# Sheet1.net
KiCad netlist of a schematic drawn in Altium Designer
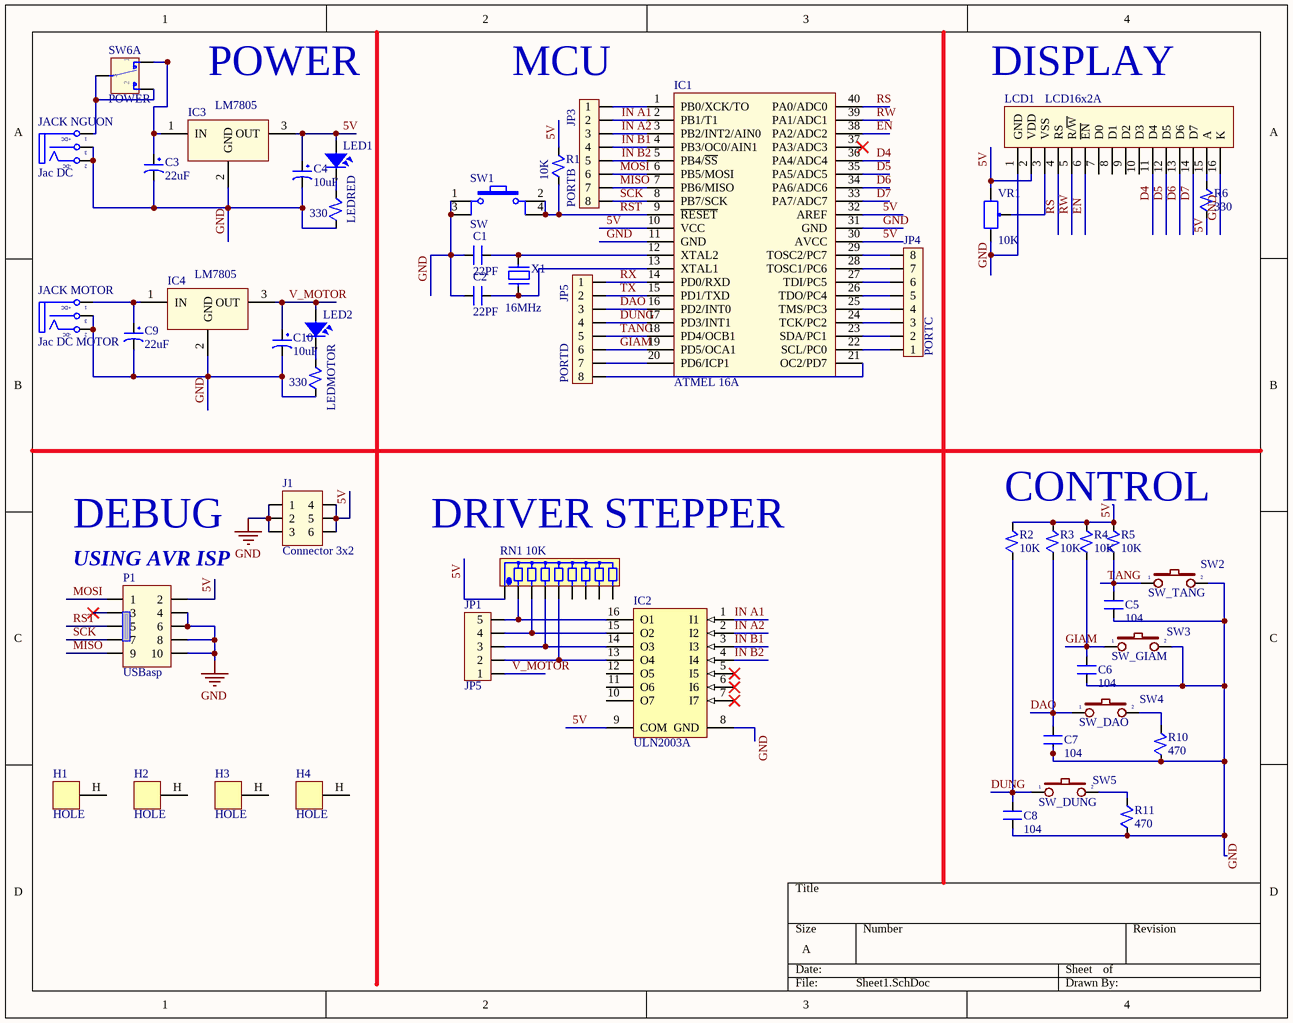
[diagram p0: Sheet1.SchDoc]

(export (version "E")
  (design (tool "Eeschema 10.0.6"))
  (components
    (comp (ref "C1")
      (value "22PF")
      (footprint "SM-0805")
      (description "Cap SMD")
      (libsource (lib "Linhkien69") (part "CM"))
    )
    (comp (ref "C2")
      (value "22PF")
      (footprint "SM-0805")
      (description "Cap SMD")
      (libsource (lib "Linhkien69") (part "CM"))
    )
    (comp (ref "C3")
      (value "22uF")
      (footprint "CP1/2")
      (description "Cap P  0,1uF < 22uF , 16 - 50V")
      (libsource (lib "Linhkien69") (part "CP1"))
    )
    (comp (ref "C4")
      (value "10uF")
      (footprint "CP1/2")
      (description "Cap P  0,1uF < 22uF , 16 - 50V")
      (libsource (lib "Linhkien69") (part "CP1"))
    )
    (comp (ref "C5")
      (value "104")
      (footprint "SM-0805")
      (description "Cap SMD")
      (libsource (lib "Linhkien69") (part "CM"))
    )
    (comp (ref "C6")
      (value "104")
      (footprint "SM-0805")
      (description "Cap SMD")
      (libsource (lib "Linhkien69") (part "CM"))
    )
    (comp (ref "C7")
      (value "104")
      (footprint "SM-0805")
      (description "Cap SMD")
      (libsource (lib "Linhkien69") (part "CM"))
    )
    (comp (ref "C8")
      (value "104")
      (footprint "SM-0805")
      (description "Cap SMD")
      (libsource (lib "Linhkien69") (part "CM"))
    )
    (comp (ref "C9")
      (value "22uF")
      (footprint "CP1/2")
      (description "Cap P  0,1uF < 22uF , 16 - 50V")
      (libsource (lib "Linhkien69") (part "CP1"))
    )
    (comp (ref "C10")
      (value "10uF")
      (footprint "CP1/2")
      (description "Cap P  0,1uF < 22uF , 16 - 50V")
      (libsource (lib "Linhkien69") (part "CP1"))
    )
    (comp (ref "H1") (value "HOLE") (footprint "HOLE") (libsource (lib "ThinhNguyenLib") (part "HOLE")))
    (comp (ref "H2") (value "HOLE") (footprint "HOLE") (libsource (lib "ThinhNguyenLib") (part "HOLE")))
    (comp (ref "H3") (value "HOLE") (footprint "HOLE") (libsource (lib "ThinhNguyenLib") (part "HOLE")))
    (comp (ref "H4") (value "HOLE") (footprint "HOLE") (libsource (lib "ThinhNguyenLib") (part "HOLE")))
    (comp (ref "IC1")
      (value "ATMEL 16A")
      (footprint "DIP40/W0.6")
      (description "8-Bit AVR Microcontroller with 16K Bytes of In-System Programmable Flash Memory")
      (libsource (lib "Linhkien69") (part "Atmega16L"))
    )
    (comp (ref "IC2")
      (value "ULN2003A")
      (footprint "DIP16/W0.3")
      (description "High-Voltage, High-Current Darlington Array")
      (fields (field (name "PUBLISHER") "Altium Limited"))
      (libsource (lib "Linhkien69") (part "ULN2003A"))
    )
    (comp (ref "IC3")
      (value "LM7805")
      (footprint "QTO-220")
      (description "On ap +, from + 5 to + 24VDC")
      (libsource (lib "Linhkien69") (part "LM78xx"))
    )
    (comp (ref "IC4")
      (value "LM7805")
      (footprint "QTO-220")
      (description "On ap +, from + 5 to + 24VDC")
      (libsource (lib "Linhkien69") (part "LM78xx"))
    )
    (comp (ref "J1")
      (value "Connector 3x2")
      (footprint "JP3x2")
      (libsource (lib "Linhkien69") (part "JP3x2"))
    )
    (comp (ref "JACK MOTOR")
      (value "Jac DC MOTOR")
      (footprint "DC-IN")
      (description "Jac DC input")
      (libsource (lib "Linhkien69") (part "DCIN"))
    )
    (comp (ref "JACK NGUON")
      (value "Jac DC")
      (footprint "DC-IN")
      (description "Jac DC input")
      (libsource (lib "Linhkien69") (part "DCIN"))
    )
    (comp (ref "JP1")
      (value "JP5")
      (footprint "CON5")
      (description "Connector 5")
      (libsource (lib "Linhkien69") (part "Con5"))
    )
    (comp (ref "JP3")
      (value "PORTB")
      (footprint "JP_CAI_8")
      (description "JP8 PIN")
      (libsource (lib "") (part "JP8_1"))
    )
    (comp (ref "JP4")
      (value "PORTC")
      (footprint "JP_CAI_8")
      (description "JP8 PIN")
      (libsource (lib "Linhkien69") (part "JP8"))
    )
    (comp (ref "JP5")
      (value "PORTD")
      (footprint "JP_CAI_8")
      (description "JP8 PIN")
      (libsource (lib "") (part "JP8_1"))
    )
    (comp (ref "LCD1")
      (value "LCD16x2A")
      (footprint "LCD16X2N")
      (description "LCD dipslay 16 char, 2 line")
      (libsource (lib "Linhkien69") (part "LCD16x2"))
    )
    (comp (ref "LED1")
      (value "LEDRED")
      (footprint "led5mm_yellow")
      (description "LED Single colour Green and Red")
      (libsource (lib "Linhkien69") (part "LED"))
    )
    (comp (ref "LED2")
      (value "LEDMOTOR")
      (footprint "led5mm_yellow")
      (description "LED Single colour Green and Red")
      (libsource (lib "Linhkien69") (part "LED"))
    )
    (comp (ref "P1")
      (value "USBasp")
      (footprint "IDE_2X5")
      (description "Header 5x2")
      (libsource (lib "Linhkien69") (part "IDE 5x2"))
    )
    (comp (ref "R1")
      (value "10K")
      (footprint "RES_0805")
      (description "res_dan")
      (libsource (lib "Linhkien69") (part "RES_0805"))
    )
    (comp (ref "R2")
      (value "10K")
      (footprint "RES_0805")
      (description "res_dan")
      (libsource (lib "Linhkien69") (part "RES_0805"))
    )
    (comp (ref "R3")
      (value "10K")
      (footprint "RES_0805")
      (description "res_dan")
      (libsource (lib "Linhkien69") (part "RES_0805"))
    )
    (comp (ref "R4")
      (value "10K")
      (footprint "RES_0805")
      (description "res_dan")
      (libsource (lib "Linhkien69") (part "RES_0805"))
    )
    (comp (ref "R5")
      (value "10K")
      (footprint "RES_0805")
      (description "res_dan")
      (libsource (lib "Linhkien69") (part "RES_0805"))
    )
    (comp (ref "R6")
      (value "330")
      (footprint "RES_0805")
      (description "res_dan")
      (libsource (lib "Linhkien69") (part "RES_0805"))
    )
    (comp (ref "R7")
      (value "330")
      (footprint "RES_0805")
      (description "res_dan")
      (libsource (lib "Linhkien69") (part "RES_0805"))
    )
    (comp (ref "R10")
      (value "470")
      (footprint "RES_0805")
      (description "res_dan")
      (libsource (lib "Linhkien69") (part "RES_0805"))
    )
    (comp (ref "R11")
      (value "470")
      (footprint "RES_0805")
      (description "res_dan")
      (libsource (lib "Linhkien69") (part "RES_0805"))
    )
    (comp (ref "R12")
      (value "330")
      (footprint "RES_0805")
      (description "res_dan")
      (libsource (lib "Linhkien69") (part "RES_0805"))
    )
    (comp (ref "RN1")
      (value "10K")
      (footprint "RN8")
      (description "Resistor 8 (Thanh)")
      (libsource (lib "Linhkien69") (part "RN8"))
    )
    (comp (ref "SW1")
      (value "SW")
      (footprint "SW4")
      (description "Switch button 4 pin")
      (libsource (lib "Linhkien69") (part "SW4"))
    )
    (comp (ref "SW2")
      (value "SW_TANG")
      (footprint "SW2")
      (description "Switch button 2 pin")
      (libsource (lib "Linhkien69") (part "SW2"))
    )
    (comp (ref "SW3")
      (value "SW_GIAM")
      (footprint "SW2")
      (description "Switch button 2 pin")
      (libsource (lib "Linhkien69") (part "SW2"))
    )
    (comp (ref "SW4")
      (value "SW_DAO")
      (footprint "SW2")
      (description "Switch button 2 pin")
      (libsource (lib "Linhkien69") (part "SW2"))
    )
    (comp (ref "SW5")
      (value "SW_DUNG")
      (footprint "SW2")
      (description "Switch button 2 pin")
      (libsource (lib "Linhkien69") (part "SW2"))
    )
    (comp (ref "SW6")
      (value "POWER")
      (footprint "SW6")
      (description "SW-DTDP - 6 Pin")
      (libsource (lib "Linhkien69") (part "SW6A"))
    )
    (comp (ref "VR1")
      (value "10K")
      (footprint "VR")
      (description "Var Resistor")
      (libsource (lib "Linhkien69") (part "VR"))
    )
    (comp (ref "X1")
      (value "16MHz")
      (footprint "XT2")
      (description "Crystal For all Crystal 2pin.")
      (libsource (lib "Linhkien69") (part "XT2"))
    )
  )
  (nets
    (net (code "1") (name "/5V") (class "Default")
      (node (ref "C4") (pin "1") (pinfunction "1_1") (pintype "passive"))
      (node (ref "IC1") (pin "10") (pinfunction "VCC_10") (pintype "passive"))
      (node (ref "IC1") (pin "30") (pinfunction "AVCC_30") (pintype "passive"))
      (node (ref "IC1") (pin "32") (pinfunction "AREF_32") (pintype "passive"))
      (node (ref "IC2") (pin "9") (pinfunction "COM_9") (pintype "passive"))
      (node (ref "IC3") (pin "3") (pinfunction "OUT_3") (pintype "passive"))
      (node (ref "J1") (pin "4") (pinfunction "4_4") (pintype "passive"))
      (node (ref "J1") (pin "5") (pinfunction "5_5") (pintype "passive"))
      (node (ref "J1") (pin "6") (pinfunction "6_6") (pintype "passive"))
      (node (ref "LCD1") (pin "2") (pinfunction "VDD_2") (pintype "passive"))
      (node (ref "LED1") (pin "1") (pinfunction "1_1") (pintype "passive"))
      (node (ref "P1") (pin "2") (pinfunction "2_2") (pintype "passive"))
      (node (ref "R1") (pin "2") (pinfunction "2_2") (pintype "passive"))
      (node (ref "R2") (pin "2") (pinfunction "2_2") (pintype "passive"))
      (node (ref "R3") (pin "2") (pinfunction "2_2") (pintype "passive"))
      (node (ref "R4") (pin "2") (pinfunction "2_2") (pintype "passive"))
      (node (ref "R5") (pin "2") (pinfunction "2_2") (pintype "passive"))
      (node (ref "R6") (pin "1") (pinfunction "1_1") (pintype "passive"))
      (node (ref "RN1") (pin "1") (pinfunction "1_1") (pintype "passive"))
      (node (ref "VR1") (pin "1") (pinfunction "1_1") (pintype "passive"))
    )
    (net (code "2") (name "/D4") (class "Default")
      (node (ref "IC1") (pin "36") (pinfunction "PA4/ADC4_36") (pintype "passive"))
      (node (ref "LCD1") (pin "11") (pinfunction "D4_11") (pintype "passive"))
    )
    (net (code "3") (name "/D5") (class "Default")
      (node (ref "IC1") (pin "35") (pinfunction "PA5/ADC5_35") (pintype "passive"))
      (node (ref "LCD1") (pin "12") (pinfunction "D5_12") (pintype "passive"))
    )
    (net (code "4") (name "/D6") (class "Default")
      (node (ref "IC1") (pin "34") (pinfunction "PA6/ADC6_34") (pintype "passive"))
      (node (ref "LCD1") (pin "13") (pinfunction "D6_13") (pintype "passive"))
    )
    (net (code "5") (name "/D7") (class "Default")
      (node (ref "IC1") (pin "33") (pinfunction "PA7/ADC7_33") (pintype "passive"))
      (node (ref "LCD1") (pin "14") (pinfunction "D7_14") (pintype "passive"))
    )
    (net (code "6") (name "/DAO") (class "Default")
      (node (ref "C7") (pin "1") (pinfunction "1_1") (pintype "passive"))
      (node (ref "IC1") (pin "16") (pinfunction "PD2/INT0_16") (pintype "passive"))
      (node (ref "JP5") (pin "3") (pinfunction "3_3") (pintype "passive"))
      (node (ref "R3") (pin "1") (pinfunction "1_1") (pintype "passive"))
      (node (ref "SW4") (pin "1") (pinfunction "1_1") (pintype "passive"))
    )
    (net (code "7") (name "/DUNG") (class "Default")
      (node (ref "C8") (pin "1") (pinfunction "1_1") (pintype "passive"))
      (node (ref "IC1") (pin "17") (pinfunction "PD3/INT1_17") (pintype "passive"))
      (node (ref "JP5") (pin "4") (pinfunction "4_4") (pintype "passive"))
      (node (ref "R2") (pin "1") (pinfunction "1_1") (pintype "passive"))
      (node (ref "SW5") (pin "1") (pinfunction "1_1") (pintype "passive"))
    )
    (net (code "8") (name "/EN") (class "Default")
      (node (ref "IC1") (pin "38") (pinfunction "PA2/ADC2_38") (pintype "passive"))
      (node (ref "LCD1") (pin "6") (pinfunction "~{EN}_6") (pintype "passive"))
    )
    (net (code "9") (name "/GIAM") (class "Default")
      (node (ref "C6") (pin "1") (pinfunction "1_1") (pintype "passive"))
      (node (ref "IC1") (pin "19") (pinfunction "PD5/OCA1_19") (pintype "passive"))
      (node (ref "JP5") (pin "6") (pinfunction "6_6") (pintype "passive"))
      (node (ref "R4") (pin "1") (pinfunction "1_1") (pintype "passive"))
      (node (ref "SW3") (pin "1") (pinfunction "1_1") (pintype "passive"))
    )
    (net (code "10") (name "/IN A1") (class "Default")
      (node (ref "IC1") (pin "2") (pinfunction "PB1/T1_2") (pintype "passive"))
      (node (ref "IC2") (pin "1") (pinfunction "I1_1") (pintype "input"))
      (node (ref "JP3") (pin "2") (pinfunction "2_2") (pintype "passive"))
    )
    (net (code "11") (name "/IN A2") (class "Default")
      (node (ref "IC1") (pin "3") (pinfunction "PB2/INT2/AIN0_3") (pintype "passive"))
      (node (ref "IC2") (pin "2") (pinfunction "I2_2") (pintype "input"))
      (node (ref "JP3") (pin "3") (pinfunction "3_3") (pintype "passive"))
    )
    (net (code "12") (name "/IN B1") (class "Default")
      (node (ref "IC1") (pin "4") (pinfunction "PB3/OC0/AIN1_4") (pintype "passive"))
      (node (ref "IC2") (pin "3") (pinfunction "I3_3") (pintype "input"))
      (node (ref "JP3") (pin "4") (pinfunction "4_4") (pintype "passive"))
    )
    (net (code "13") (name "/IN B2") (class "Default")
      (node (ref "IC1") (pin "5") (pinfunction "PB4/~{SS}_5") (pintype "passive"))
      (node (ref "IC2") (pin "4") (pinfunction "I4_4") (pintype "input"))
      (node (ref "JP3") (pin "5") (pinfunction "5_5") (pintype "passive"))
    )
    (net (code "14") (name "/MISO") (class "Default")
      (node (ref "IC1") (pin "7") (pinfunction "PB6/MISO_7") (pintype "passive"))
      (node (ref "JP3") (pin "7") (pinfunction "7_7") (pintype "passive"))
      (node (ref "P1") (pin "9") (pinfunction "9_9") (pintype "passive"))
    )
    (net (code "15") (name "/MOSI") (class "Default")
      (node (ref "IC1") (pin "6") (pinfunction "PB5/MOSI_6") (pintype "passive"))
      (node (ref "JP3") (pin "6") (pinfunction "6_6") (pintype "passive"))
      (node (ref "P1") (pin "1") (pinfunction "1_1") (pintype "passive"))
    )
    (net (code "16") (name "/RS") (class "Default")
      (node (ref "IC1") (pin "40") (pinfunction "PA0/ADC0_40") (pintype "passive"))
      (node (ref "LCD1") (pin "4") (pinfunction "RS_4") (pintype "passive"))
    )
    (net (code "17") (name "/RST") (class "Default")
      (node (ref "IC1") (pin "9") (pinfunction "~{RESET}_9") (pintype "passive"))
      (node (ref "P1") (pin "5") (pinfunction "5_5") (pintype "passive"))
      (node (ref "R1") (pin "1") (pinfunction "1_1") (pintype "passive"))
      (node (ref "SW1") (pin "2") (pintype "passive"))
      (node (ref "SW1") (pin "4") (pinfunction "4_4") (pintype "passive"))
    )
    (net (code "18") (name "/RW") (class "Default")
      (node (ref "IC1") (pin "39") (pinfunction "PA1/ADC1_39") (pintype "passive"))
      (node (ref "LCD1") (pin "5") (pinfunction "R/~{W}_5") (pintype "passive"))
    )
    (net (code "19") (name "/RX") (class "Default")
      (node (ref "IC1") (pin "14") (pinfunction "PD0/RXD_14") (pintype "passive"))
      (node (ref "JP5") (pin "1") (pinfunction "1_1") (pintype "passive"))
    )
    (net (code "20") (name "/SCK") (class "Default")
      (node (ref "IC1") (pin "8") (pinfunction "PB7/SCK_8") (pintype "passive"))
      (node (ref "JP3") (pin "8") (pinfunction "8_8") (pintype "passive"))
      (node (ref "P1") (pin "7") (pinfunction "7_7") (pintype "passive"))
    )
    (net (code "21") (name "/TANG") (class "Default")
      (node (ref "C5") (pin "1") (pinfunction "1_1") (pintype "passive"))
      (node (ref "IC1") (pin "18") (pinfunction "PD4/OCB1_18") (pintype "passive"))
      (node (ref "JP5") (pin "5") (pinfunction "5_5") (pintype "passive"))
      (node (ref "R5") (pin "1") (pinfunction "1_1") (pintype "passive"))
      (node (ref "SW2") (pin "1") (pinfunction "1_1") (pintype "passive"))
    )
    (net (code "22") (name "/TX") (class "Default")
      (node (ref "IC1") (pin "15") (pinfunction "PD1/TXD_15") (pintype "passive"))
      (node (ref "JP5") (pin "2") (pinfunction "2_2") (pintype "passive"))
    )
    (net (code "23") (name "/V_MOTOR") (class "Default")
      (node (ref "C10") (pin "1") (pinfunction "1_1") (pintype "passive"))
      (node (ref "IC4") (pin "3") (pinfunction "OUT_3") (pintype "passive"))
      (node (ref "JP1") (pin "1") (pinfunction "1_1") (pintype "passive"))
      (node (ref "LED2") (pin "1") (pinfunction "1_1") (pintype "passive"))
    )
    (net (code "24") (name "GND") (class "Default")
      (node (ref "C1") (pin "1") (pinfunction "1_1") (pintype "passive"))
      (node (ref "C10") (pin "2") (pinfunction "2_2") (pintype "passive"))
      (node (ref "C2") (pin "1") (pinfunction "1_1") (pintype "passive"))
      (node (ref "C3") (pin "2") (pinfunction "2_2") (pintype "passive"))
      (node (ref "C4") (pin "2") (pinfunction "2_2") (pintype "passive"))
      (node (ref "C5") (pin "2") (pinfunction "2_2") (pintype "passive"))
      (node (ref "C6") (pin "2") (pinfunction "2_2") (pintype "passive"))
      (node (ref "C7") (pin "2") (pinfunction "2_2") (pintype "passive"))
      (node (ref "C8") (pin "2") (pinfunction "2_2") (pintype "passive"))
      (node (ref "C9") (pin "2") (pinfunction "2_2") (pintype "passive"))
      (node (ref "IC1") (pin "11") (pinfunction "GND_11") (pintype "passive"))
      (node (ref "IC1") (pin "31") (pinfunction "GND_31") (pintype "passive"))
      (node (ref "IC2") (pin "8") (pinfunction "GND_8") (pintype "power_in"))
      (node (ref "IC3") (pin "2") (pinfunction "GND_2") (pintype "passive"))
      (node (ref "IC4") (pin "2") (pinfunction "GND_2") (pintype "passive"))
      (node (ref "J1") (pin "1") (pinfunction "1_1") (pintype "passive"))
      (node (ref "J1") (pin "2") (pinfunction "2_2") (pintype "passive"))
      (node (ref "J1") (pin "3") (pinfunction "3_3") (pintype "passive"))
      (node (ref "JACK MOTOR") (pin "2") (pinfunction "TN_2") (pintype "passive"))
      (node (ref "JACK MOTOR") (pin "3") (pinfunction "S_3") (pintype "power_in"))
      (node (ref "JACK NGUON") (pin "2") (pinfunction "TN_2") (pintype "passive"))
      (node (ref "JACK NGUON") (pin "3") (pinfunction "S_3") (pintype "power_in"))
      (node (ref "LCD1") (pin "1") (pinfunction "GND_1") (pintype "passive"))
      (node (ref "LCD1") (pin "16") (pinfunction "K_16") (pintype "passive"))
      (node (ref "P1") (pin "10") (pinfunction "10_10") (pintype "passive"))
      (node (ref "P1") (pin "4") (pinfunction "4_4") (pintype "passive"))
      (node (ref "P1") (pin "6") (pinfunction "6_6") (pintype "passive"))
      (node (ref "P1") (pin "8") (pinfunction "8_8") (pintype "passive"))
      (node (ref "R10") (pin "1") (pinfunction "1_1") (pintype "passive"))
      (node (ref "R11") (pin "1") (pinfunction "1_1") (pintype "passive"))
      (node (ref "R12") (pin "1") (pinfunction "1_1") (pintype "passive"))
      (node (ref "R7") (pin "1") (pinfunction "1_1") (pintype "passive"))
      (node (ref "SW1") (pin "1") (pintype "passive"))
      (node (ref "SW1") (pin "3") (pinfunction "3_3") (pintype "passive"))
      (node (ref "SW2") (pin "2") (pinfunction "2_2") (pintype "passive"))
      (node (ref "SW3") (pin "2") (pinfunction "2_2") (pintype "passive"))
      (node (ref "VR1") (pin "3") (pinfunction "3_3") (pintype "passive"))
    )
    (net (code "25") (name "Net-(IC1-OC2{slash}PD7)") (class "Default")
      (node (ref "IC1") (pin "21") (pinfunction "OC2/PD7_21") (pintype "passive"))
      (node (ref "JP5") (pin "8") (pinfunction "8_8") (pintype "passive"))
    )
    (net (code "26") (name "Net-(IC1-PB0{slash}XCK{slash}TO)") (class "Default")
      (node (ref "IC1") (pin "1") (pinfunction "PB0/XCK/TO_1") (pintype "passive"))
      (node (ref "JP3") (pin "1") (pinfunction "1_1") (pintype "passive"))
    )
    (net (code "27") (name "Net-(IC1-PD6{slash}ICP1)") (class "Default")
      (node (ref "IC1") (pin "20") (pinfunction "PD6/ICP1_20") (pintype "passive"))
      (node (ref "JP5") (pin "7") (pinfunction "7_7") (pintype "passive"))
    )
    (net (code "28") (name "Net-(IC1-SCL{slash}PC0)") (class "Default")
      (node (ref "IC1") (pin "22") (pinfunction "SCL/PC0_22") (pintype "passive"))
      (node (ref "JP4") (pin "1") (pinfunction "1_1") (pintype "passive"))
    )
    (net (code "29") (name "Net-(IC1-SDA{slash}PC1)") (class "Default")
      (node (ref "IC1") (pin "23") (pinfunction "SDA/PC1_23") (pintype "passive"))
      (node (ref "JP4") (pin "2") (pinfunction "2_2") (pintype "passive"))
    )
    (net (code "30") (name "Net-(IC1-TCK{slash}PC2)") (class "Default")
      (node (ref "IC1") (pin "24") (pinfunction "TCK/PC2_24") (pintype "passive"))
      (node (ref "JP4") (pin "3") (pinfunction "3_3") (pintype "passive"))
    )
    (net (code "31") (name "Net-(IC1-TDI{slash}PC5)") (class "Default")
      (node (ref "IC1") (pin "27") (pinfunction "TDI/PC5_27") (pintype "passive"))
      (node (ref "JP4") (pin "6") (pinfunction "6_6") (pintype "passive"))
    )
    (net (code "32") (name "Net-(IC1-TDO{slash}PC4)") (class "Default")
      (node (ref "IC1") (pin "26") (pinfunction "TDO/PC4_26") (pintype "passive"))
      (node (ref "JP4") (pin "5") (pinfunction "5_5") (pintype "passive"))
    )
    (net (code "33") (name "Net-(IC1-TMS{slash}PC3)") (class "Default")
      (node (ref "IC1") (pin "25") (pinfunction "TMS/PC3_25") (pintype "passive"))
      (node (ref "JP4") (pin "4") (pinfunction "4_4") (pintype "passive"))
    )
    (net (code "34") (name "Net-(IC1-TOSC1{slash}PC6)") (class "Default")
      (node (ref "IC1") (pin "28") (pinfunction "TOSC1/PC6_28") (pintype "passive"))
      (node (ref "JP4") (pin "7") (pinfunction "7_7") (pintype "passive"))
    )
    (net (code "35") (name "Net-(IC1-TOSC2{slash}PC7)") (class "Default")
      (node (ref "IC1") (pin "29") (pinfunction "TOSC2/PC7_29") (pintype "passive"))
      (node (ref "JP4") (pin "8") (pinfunction "8_8") (pintype "passive"))
    )
    (net (code "36") (name "Net-(IC1-XTAL1)") (class "Default")
      (node (ref "C2") (pin "2") (pinfunction "2_2") (pintype "passive"))
      (node (ref "IC1") (pin "13") (pinfunction "XTAL1_13") (pintype "passive"))
      (node (ref "X1") (pin "1") (pinfunction "1_1") (pintype "passive"))
    )
    (net (code "37") (name "Net-(IC1-XTAL2)") (class "Default")
      (node (ref "C1") (pin "2") (pinfunction "2_2") (pintype "passive"))
      (node (ref "IC1") (pin "12") (pinfunction "XTAL2_12") (pintype "passive"))
      (node (ref "X1") (pin "2") (pinfunction "2_2") (pintype "passive"))
    )
    (net (code "38") (name "Net-(IC2-O1)") (class "Default")
      (node (ref "IC2") (pin "16") (pinfunction "O1_16") (pintype "open_collector"))
      (node (ref "JP1") (pin "5") (pinfunction "5_5") (pintype "passive"))
      (node (ref "RN1") (pin "2") (pinfunction "2_2") (pintype "passive"))
    )
    (net (code "39") (name "Net-(IC2-O2)") (class "Default")
      (node (ref "IC2") (pin "15") (pinfunction "O2_15") (pintype "open_collector"))
      (node (ref "JP1") (pin "4") (pinfunction "4_4") (pintype "passive"))
      (node (ref "RN1") (pin "3") (pinfunction "3_3") (pintype "passive"))
    )
    (net (code "40") (name "Net-(IC2-O3)") (class "Default")
      (node (ref "IC2") (pin "14") (pinfunction "O3_14") (pintype "open_collector"))
      (node (ref "JP1") (pin "3") (pinfunction "3_3") (pintype "passive"))
      (node (ref "RN1") (pin "4") (pinfunction "4_4") (pintype "passive"))
    )
    (net (code "41") (name "Net-(IC2-O4)") (class "Default")
      (node (ref "IC2") (pin "13") (pinfunction "O4_13") (pintype "open_collector"))
      (node (ref "JP1") (pin "2") (pinfunction "2_2") (pintype "passive"))
      (node (ref "RN1") (pin "5") (pinfunction "5_5") (pintype "passive"))
    )
    (net (code "42") (name "Net-(IC3-IN)") (class "Default")
      (node (ref "C3") (pin "1") (pinfunction "1_1") (pintype "passive"))
      (node (ref "IC3") (pin "1") (pinfunction "IN_1") (pintype "passive"))
      (node (ref "SW6") (pin "1") (pinfunction "1_1") (pintype "passive"))
    )
    (net (code "43") (name "Net-(IC4-IN)") (class "Default")
      (node (ref "C9") (pin "1") (pinfunction "1_1") (pintype "passive"))
      (node (ref "IC4") (pin "1") (pinfunction "IN_1") (pintype "passive"))
      (node (ref "JACK MOTOR") (pin "1") (pinfunction "T_1") (pintype "passive"))
    )
    (net (code "44") (name "Net-(JACK NGUON-T)") (class "Default")
      (node (ref "JACK NGUON") (pin "1") (pinfunction "T_1") (pintype "passive"))
      (node (ref "SW6") (pin "2") (pinfunction "2_2") (pintype "passive"))
      (node (ref "SW6") (pin "3") (pinfunction "3_3") (pintype "passive"))
    )
    (net (code "45") (name "Net-(LCD1-A)") (class "Default")
      (node (ref "LCD1") (pin "15") (pinfunction "A_15") (pintype "passive"))
      (node (ref "R6") (pin "2") (pinfunction "2_2") (pintype "passive"))
    )
    (net (code "46") (name "Net-(LCD1-VSS)") (class "Default")
      (node (ref "LCD1") (pin "3") (pinfunction "VSS_3") (pintype "passive"))
      (node (ref "VR1") (pin "2") (pinfunction "2_2") (pintype "passive"))
    )
    (net (code "47") (name "Net-(LED1-Pad2)") (class "Default")
      (node (ref "LED1") (pin "2") (pinfunction "2_2") (pintype "passive"))
      (node (ref "R7") (pin "2") (pinfunction "2_2") (pintype "passive"))
    )
    (net (code "48") (name "Net-(LED2-Pad2)") (class "Default")
      (node (ref "LED2") (pin "2") (pinfunction "2_2") (pintype "passive"))
      (node (ref "R12") (pin "2") (pinfunction "2_2") (pintype "passive"))
    )
    (net (code "49") (name "Net-(R10-Pad2)") (class "Default")
      (node (ref "R10") (pin "2") (pinfunction "2_2") (pintype "passive"))
      (node (ref "SW4") (pin "2") (pinfunction "2_2") (pintype "passive"))
    )
    (net (code "50") (name "Net-(R11-Pad2)") (class "Default")
      (node (ref "R11") (pin "2") (pinfunction "2_2") (pintype "passive"))
      (node (ref "SW5") (pin "2") (pinfunction "2_2") (pintype "passive"))
    )
    (net (code "51") (name "unconnected-(H1-HOLE-PadH)") (class "Default")
      (node (ref "H1") (pin "H") (pinfunction "HOLE_H") (pintype "passive"))
    )
    (net (code "52") (name "unconnected-(H2-HOLE-PadH)") (class "Default")
      (node (ref "H2") (pin "H") (pinfunction "HOLE_H") (pintype "passive"))
    )
    (net (code "53") (name "unconnected-(H3-HOLE-PadH)") (class "Default")
      (node (ref "H3") (pin "H") (pinfunction "HOLE_H") (pintype "passive"))
    )
    (net (code "54") (name "unconnected-(H4-HOLE-PadH)") (class "Default")
      (node (ref "H4") (pin "H") (pinfunction "HOLE_H") (pintype "passive"))
    )
    (net (code "55") (name "unconnected-(IC1-PA3{slash}ADC3-Pad37)") (class "Default")
      (node (ref "IC1") (pin "37") (pinfunction "PA3/ADC3_37") (pintype "passive+no_connect"))
    )
    (net (code "56") (name "unconnected-(IC2-I5-Pad5)") (class "Default")
      (node (ref "IC2") (pin "5") (pinfunction "I5_5") (pintype "input+no_connect"))
    )
    (net (code "57") (name "unconnected-(IC2-I6-Pad6)") (class "Default")
      (node (ref "IC2") (pin "6") (pinfunction "I6_6") (pintype "input+no_connect"))
    )
    (net (code "58") (name "unconnected-(IC2-I7-Pad7)") (class "Default")
      (node (ref "IC2") (pin "7") (pinfunction "I7_7") (pintype "input+no_connect"))
    )
    (net (code "59") (name "unconnected-(IC2-O5-Pad12)") (class "Default")
      (node (ref "IC2") (pin "12") (pinfunction "O5_12") (pintype "open_collector"))
    )
    (net (code "60") (name "unconnected-(IC2-O6-Pad11)") (class "Default")
      (node (ref "IC2") (pin "11") (pinfunction "O6_11") (pintype "open_collector"))
    )
    (net (code "61") (name "unconnected-(IC2-O7-Pad10)") (class "Default")
      (node (ref "IC2") (pin "10") (pinfunction "O7_10") (pintype "open_collector"))
    )
    (net (code "62") (name "unconnected-(LCD1-D0-Pad7)") (class "Default")
      (node (ref "LCD1") (pin "7") (pinfunction "D0_7") (pintype "passive"))
    )
    (net (code "63") (name "unconnected-(LCD1-D1-Pad8)") (class "Default")
      (node (ref "LCD1") (pin "8") (pinfunction "D1_8") (pintype "passive"))
    )
    (net (code "64") (name "unconnected-(LCD1-D2-Pad9)") (class "Default")
      (node (ref "LCD1") (pin "9") (pinfunction "D2_9") (pintype "passive"))
    )
    (net (code "65") (name "unconnected-(LCD1-D3-Pad10)") (class "Default")
      (node (ref "LCD1") (pin "10") (pinfunction "D3_10") (pintype "passive"))
    )
    (net (code "66") (name "unconnected-(P1-Pad3)") (class "Default")
      (node (ref "P1") (pin "3") (pinfunction "3_3") (pintype "passive+no_connect"))
    )
    (net (code "67") (name "unconnected-(RN1-Pad6)") (class "Default")
      (node (ref "RN1") (pin "6") (pinfunction "6_6") (pintype "passive"))
    )
    (net (code "68") (name "unconnected-(RN1-Pad7)") (class "Default")
      (node (ref "RN1") (pin "7") (pinfunction "7_7") (pintype "passive"))
    )
    (net (code "69") (name "unconnected-(RN1-Pad8)") (class "Default")
      (node (ref "RN1") (pin "8") (pinfunction "8_8") (pintype "passive"))
    )
    (net (code "70") (name "unconnected-(RN1-Pad9)") (class "Default")
      (node (ref "RN1") (pin "9") (pinfunction "9_9") (pintype "passive"))
    )
  )
)
